# Adafruit_Metro_ESP32-S2.net
KiCad netlist of a schematic drawn in EAGLE
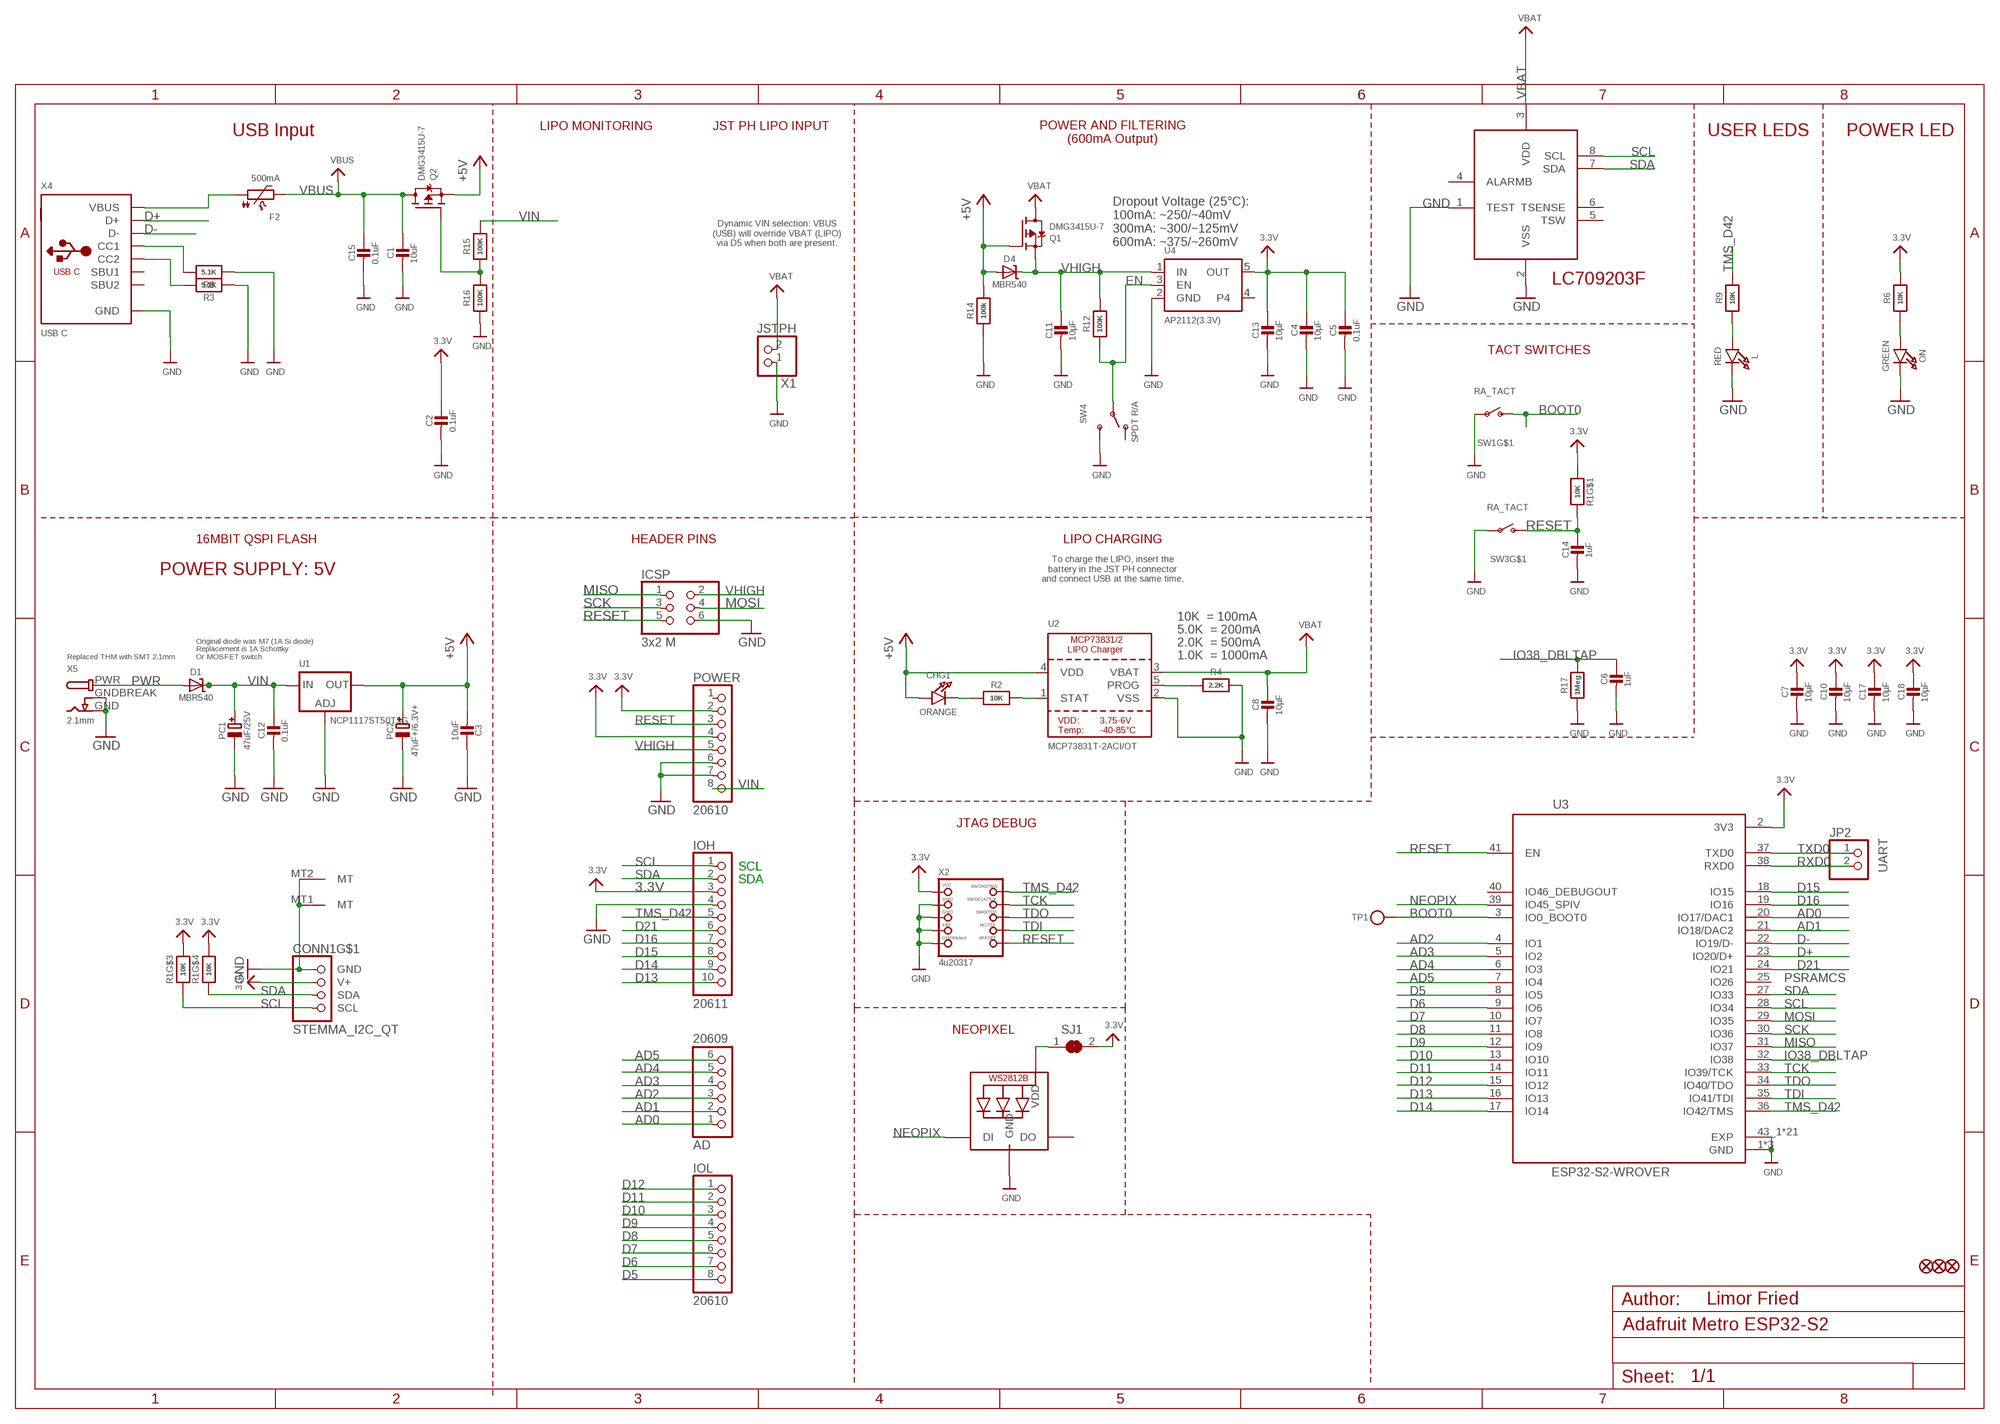
[diagram p0: schematic, sheet 1]

(export (version "E")
  (design (tool "Eeschema 10.0.6"))
  (components
    (comp (ref "AD")
      (value "20609")
      (footprint "eagle-import:1X06_OVALWAVE")
      (libsource (lib "eagle-import") (part "HEADER-1X6OVALWAVE"))
    )
    (comp (ref "C1")
      (value "10uF")
      (footprint "eagle-import:0805-NO")
      (libsource (lib "eagle-import") (part "CAP_CERAMIC0805-NOOUTLINE"))
    )
    (comp (ref "C2")
      (value "0.1uF")
      (footprint "eagle-import:0603-NO")
      (libsource (lib "eagle-import") (part "CAP_CERAMIC0603_NO"))
    )
    (comp (ref "C3")
      (value "10uF")
      (footprint "eagle-import:0805-NO")
      (libsource (lib "eagle-import") (part "CAP_CERAMIC0805-NOOUTLINE"))
    )
    (comp (ref "C4")
      (value "10µF")
      (footprint "eagle-import:0805-NO")
      (libsource (lib "eagle-import") (part "CAP_CERAMIC0805-NOOUTLINE"))
    )
    (comp (ref "C5")
      (value "0.1uF")
      (footprint "eagle-import:0603-NO")
      (libsource (lib "eagle-import") (part "CAP_CERAMIC0603_NO"))
    )
    (comp (ref "C6")
      (value "1uF")
      (footprint "eagle-import:0603-NO")
      (libsource (lib "eagle-import") (part "CAP_CERAMIC0603_NO"))
    )
    (comp (ref "C7")
      (value "10µF")
      (footprint "eagle-import:0805-NO")
      (libsource (lib "eagle-import") (part "CAP_CERAMIC0805-NOOUTLINE"))
    )
    (comp (ref "C8")
      (value "10µF")
      (footprint "eagle-import:0805-NO")
      (libsource (lib "eagle-import") (part "CAP_CERAMIC0805-NOOUTLINE"))
    )
    (comp (ref "C10")
      (value "10µF")
      (footprint "eagle-import:0805-NO")
      (libsource (lib "eagle-import") (part "CAP_CERAMIC0805-NOOUTLINE"))
    )
    (comp (ref "C11")
      (value "10µF")
      (footprint "eagle-import:0805-NO")
      (libsource (lib "eagle-import") (part "CAP_CERAMIC0805-NOOUTLINE"))
    )
    (comp (ref "C12")
      (value "0.1uF")
      (footprint "eagle-import:0603-NO")
      (libsource (lib "eagle-import") (part "CAP_CERAMIC0603_NO"))
    )
    (comp (ref "C13")
      (value "10µF")
      (footprint "eagle-import:0805-NO")
      (libsource (lib "eagle-import") (part "CAP_CERAMIC0805-NOOUTLINE"))
    )
    (comp (ref "C14")
      (value "1uF")
      (footprint "eagle-import:0603-NO")
      (libsource (lib "eagle-import") (part "CAP_CERAMIC0603_NO"))
    )
    (comp (ref "C15")
      (value "0.1uF")
      (footprint "eagle-import:0603-NO")
      (libsource (lib "eagle-import") (part "CAP_CERAMIC0603_NO"))
    )
    (comp (ref "C17")
      (value "10µF")
      (footprint "eagle-import:0805-NO")
      (libsource (lib "eagle-import") (part "CAP_CERAMIC0805-NOOUTLINE"))
    )
    (comp (ref "C18")
      (value "10µF")
      (footprint "eagle-import:0805-NO")
      (libsource (lib "eagle-import") (part "CAP_CERAMIC0805-NOOUTLINE"))
    )
    (comp (ref "CHG1")
      (value "ORANGE")
      (footprint "eagle-import:CHIPLED_0603_NOOUTLINE")
      (libsource (lib "eagle-import") (part "LED0603_NOOUTLINE"))
    )
    (comp (ref "CONN1")
      (value "STEMMA_I2C_QT")
      (footprint "eagle-import:JST_SH4")
      (libsource (lib "eagle-import") (part "STEMMA_I2C_QT"))
    )
    (comp (ref "D1")
      (value "MBR540")
      (footprint "eagle-import:SOD-123")
      (libsource (lib "eagle-import") (part "DIODE-SCHOTTKYSOD-123"))
    )
    (comp (ref "D4")
      (value "MBR540")
      (footprint "eagle-import:SOD-123")
      (libsource (lib "eagle-import") (part "DIODE-SCHOTTKYSOD-123"))
    )
    (comp (ref "F2")
      (value "500mA")
      (footprint "eagle-import:1206")
      (libsource (lib "eagle-import") (part "PTC1206"))
    )
    (comp (ref "FD1")
      (value "FIDUCIAL_1MM")
      (footprint "eagle-import:FIDUCIAL_1MM")
      (libsource (lib "eagle-import") (part "FIDUCIAL_1MM"))
    )
    (comp (ref "FD2")
      (value "FIDUCIAL_1MM")
      (footprint "eagle-import:FIDUCIAL_1MM")
      (libsource (lib "eagle-import") (part "FIDUCIAL_1MM"))
    )
    (comp (ref "FD3")
      (value "FIDUCIAL_1MM")
      (footprint "eagle-import:FIDUCIAL_1MM")
      (libsource (lib "eagle-import") (part "FIDUCIAL_1MM"))
    )
    (comp (ref "IC2")
      (value "LC709203F")
      (footprint "eagle-import:WDFN8_3X4_0.65")
      (libsource (lib "eagle-import") (part "LC709203F"))
    )
    (comp (ref "ICSP")
      (value "3x2 M")
      (footprint "eagle-import:2X03_ROUND_70MIL")
      (libsource (lib "eagle-import") (part "HEADER-2X3"))
    )
    (comp (ref "IOH")
      (value "20611")
      (footprint "eagle-import:1X10_OVALWAVE")
      (libsource (lib "eagle-import") (part "HEADER-1X10OVALWAVE"))
    )
    (comp (ref "IOL")
      (value "20610")
      (footprint "eagle-import:1X08_OVALWAVE")
      (libsource (lib "eagle-import") (part "HEADER-1X8OVALWAVE"))
    )
    (comp (ref "JP2")
      (value "UART")
      (footprint "eagle-import:1X02_ROUND")
      (libsource (lib "eagle-import") (part "HEADER-1X2ROUND"))
    )
    (comp (ref "L")
      (value "RED")
      (footprint "eagle-import:CHIPLED_0603_NOOUTLINE")
      (libsource (lib "eagle-import") (part "LED0603_NOOUTLINE"))
    )
    (comp (ref "LED1")
      (value "WS2812B3535")
      (footprint "eagle-import:LED3535")
      (libsource (lib "eagle-import") (part "WS2812B3535"))
    )
    (comp (ref "ON")
      (value "GREEN")
      (footprint "eagle-import:CHIPLED_0603_NOOUTLINE")
      (libsource (lib "eagle-import") (part "LED0603_NOOUTLINE"))
    )
    (comp (ref "PC1")
      (value "47uF/25V")
      (footprint "eagle-import:PANASONIC_D")
      (libsource (lib "eagle-import") (part "CAP_ELECTROLYTICPANASONIC_D"))
    )
    (comp (ref "PC2")
      (value "47uF+/6.3V+")
      (footprint "eagle-import:PANASONIC_D")
      (libsource (lib "eagle-import") (part "CAP_ELECTROLYTICPANASONIC_D"))
    )
    (comp (ref "POWER")
      (value "20610")
      (footprint "eagle-import:1X08_OVALWAVE")
      (libsource (lib "eagle-import") (part "HEADER-1X8OVALWAVE"))
    )
    (comp (ref "Q1")
      (value "DMG3415U-7")
      (footprint "eagle-import:SOT23-R")
      (libsource (lib "eagle-import") (part "MOSFET-P"))
    )
    (comp (ref "Q2")
      (value "DMG3415U-7")
      (footprint "eagle-import:SOT23-R")
      (libsource (lib "eagle-import") (part "MOSFET-P"))
    )
    (comp (ref "R1")
      (value "10K")
      (footprint "eagle-import:RESPACK_4X0603")
      (libsource (lib "eagle-import") (part "RESISTOR_4PACK"))
    )
    (comp (ref "R2")
      (value "10K")
      (footprint "eagle-import:0603-NO")
      (libsource (lib "eagle-import") (part "RESISTOR_0603_NOOUT"))
    )
    (comp (ref "R3")
      (value "5.1K")
      (footprint "eagle-import:0603-NO")
      (libsource (lib "eagle-import") (part "RESISTOR_0603_NOOUT"))
    )
    (comp (ref "R4")
      (value "2.2K")
      (footprint "eagle-import:0603-NO")
      (libsource (lib "eagle-import") (part "RESISTOR_0603_NOOUT"))
    )
    (comp (ref "R6")
      (value "10K")
      (footprint "eagle-import:0603-NO")
      (libsource (lib "eagle-import") (part "RESISTOR_0603_NOOUT"))
    )
    (comp (ref "R8")
      (value "5.1K")
      (footprint "eagle-import:0603-NO")
      (libsource (lib "eagle-import") (part "RESISTOR_0603_NOOUT"))
    )
    (comp (ref "R9")
      (value "10K")
      (footprint "eagle-import:0603-NO")
      (libsource (lib "eagle-import") (part "RESISTOR_0603_NOOUT"))
    )
    (comp (ref "R12")
      (value "100K")
      (footprint "eagle-import:0603-NO")
      (libsource (lib "eagle-import") (part "RESISTOR_0603_NOOUT"))
    )
    (comp (ref "R14")
      (value "100k")
      (footprint "eagle-import:0603-NO")
      (libsource (lib "eagle-import") (part "RESISTOR_0603_NOOUT"))
    )
    (comp (ref "R15")
      (value "100K")
      (footprint "eagle-import:0603-NO")
      (libsource (lib "eagle-import") (part "RESISTOR_0603_NOOUT"))
    )
    (comp (ref "R16")
      (value "100K")
      (footprint "eagle-import:0603-NO")
      (libsource (lib "eagle-import") (part "RESISTOR_0603_NOOUT"))
    )
    (comp (ref "R17")
      (value "1Meg")
      (footprint "eagle-import:0603-NO")
      (libsource (lib "eagle-import") (part "RESISTOR_0603_NOOUT"))
    )
    (comp (ref "SJ1")
      (value "SOLDERJUMPER_CLOSED")
      (footprint "eagle-import:SOLDERJUMPER_CLOSEDWIRE")
      (libsource (lib "eagle-import") (part "SOLDERJUMPER_CLOSED"))
    )
    (comp (ref "SW1")
      (value "RA_TACT")
      (footprint "eagle-import:SPST_TACTILE_RA")
      (libsource (lib "eagle-import") (part "SWITCH_SPST_TACT_RA"))
    )
    (comp (ref "SW3")
      (value "RA_TACT")
      (footprint "eagle-import:SPST_TACTILE_RA")
      (libsource (lib "eagle-import") (part "SWITCH_SPST_TACT_RA"))
    )
    (comp (ref "SW4")
      (value "SPDT R/A")
      (footprint "eagle-import:SPDT_SMT_SSSS811101")
      (libsource (lib "eagle-import") (part "SWITCH_SPDT"))
    )
    (comp (ref "TP1")
      (value "TESTPOINTROUND1.5MMNO")
      (footprint "eagle-import:TESTPOINT_ROUND_1.5MM_NO")
      (libsource (lib "eagle-import") (part "TESTPOINTROUND1.5MMNO"))
    )
    (comp (ref "U1")
      (value "NCP1117ST50T3G")
      (footprint "eagle-import:SOT223-R")
      (libsource (lib "eagle-import") (part "LM1117SOT223-REFLOW"))
    )
    (comp (ref "U2")
      (value "MCP73831T-2ACI/OT")
      (footprint "eagle-import:SOT23-5")
      (libsource (lib "eagle-import") (part "MCP73831/2"))
    )
    (comp (ref "U3")
      (value "ESP32-S2-WROVER")
      (footprint "eagle-import:MODULE_ESP32-S2-WROVER")
      (fields (field (name "MF") "Espressif Systems"))
      (libsource (lib "eagle-import") (part "ESP32-S2-WROVER"))
    )
    (comp (ref "U4")
      (value "AP2112(3.3V)")
      (footprint "eagle-import:SOT23-5")
      (libsource (lib "eagle-import") (part "VREG_SOT23-5"))
    )
    (comp (ref "X1")
      (value "JSTPH")
      (footprint "eagle-import:JSTPH2_BATT")
      (libsource (lib "eagle-import") (part "CON_JST_PH_2PIN_BATT"))
    )
    (comp (ref "X2")
      (value "4u20317")
      (footprint "eagle-import:2X05_1.27MM_BOX_POSTS")
      (libsource (lib "eagle-import") (part "JTAG-CORTEXBOXPOSTS"))
    )
    (comp (ref "X4")
      (value "USB C")
      (footprint "eagle-import:USB_C_CUSB31-CFM2AX-01-X")
      (libsource (lib "eagle-import") (part "USB_C"))
    )
    (comp (ref "X5")
      (value "2.1mm")
      (footprint "eagle-import:DCJACK_2MM_PTH")
      (libsource (lib "eagle-import") (part "DCBARRELPTH"))
    )
  )
  (nets
    (net (code "1") (name "+5V") (class "Default")
      (node (ref "C3") (pin "2") (pinfunction "2_2") (pintype "passive"))
      (node (ref "CHG1") (pin "A") (pinfunction "A_A") (pintype "passive"))
      (node (ref "D4") (pin "A") (pinfunction "A_A") (pintype "passive"))
      (node (ref "PC2") (pin "+") (pinfunction "+_+") (pintype "passive"))
      (node (ref "Q1") (pin "1") (pinfunction "G_1") (pintype "passive"))
      (node (ref "Q2") (pin "2") (pinfunction "S_2") (pintype "passive"))
      (node (ref "R14") (pin "2") (pinfunction "2_2") (pintype "passive"))
      (node (ref "U1") (pin "2") (pinfunction "OUT_2") (pintype "passive"))
      (node (ref "U1") (pin "4") (pinfunction "OUT_4") (pintype "passive"))
      (node (ref "U2") (pin "4") (pinfunction "VDD_4") (pintype "power_in"))
    )
    (net (code "2") (name "/AD0") (class "Default")
      (node (ref "AD") (pin "1") (pinfunction "1_1") (pintype "passive"))
      (node (ref "U3") (pin "20") (pinfunction "IO17/DAC1_20") (pintype "bidirectional"))
    )
    (net (code "3") (name "/AD1") (class "Default")
      (node (ref "AD") (pin "2") (pinfunction "2_2") (pintype "passive"))
      (node (ref "U3") (pin "21") (pinfunction "IO18/DAC2_21") (pintype "bidirectional"))
    )
    (net (code "4") (name "/AD2") (class "Default")
      (node (ref "AD") (pin "3") (pinfunction "3_3") (pintype "passive"))
      (node (ref "U3") (pin "4") (pinfunction "IO1_4") (pintype "bidirectional"))
    )
    (net (code "5") (name "/AD3") (class "Default")
      (node (ref "AD") (pin "4") (pinfunction "4_4") (pintype "passive"))
      (node (ref "U3") (pin "5") (pinfunction "IO2_5") (pintype "bidirectional"))
    )
    (net (code "6") (name "/AD4") (class "Default")
      (node (ref "AD") (pin "5") (pinfunction "5_5") (pintype "passive"))
      (node (ref "U3") (pin "6") (pinfunction "IO3_6") (pintype "bidirectional"))
    )
    (net (code "7") (name "/AD5") (class "Default")
      (node (ref "AD") (pin "6") (pinfunction "6_6") (pintype "passive"))
      (node (ref "U3") (pin "7") (pinfunction "IO4_7") (pintype "bidirectional"))
    )
    (net (code "8") (name "/BOOT0") (class "Default")
      (node (ref "SW1") (pin "2") (pinfunction "S_2") (pintype "passive"))
      (node (ref "TP1") (pin "P$1") (pinfunction "P$1_P$1") (pintype "bidirectional"))
      (node (ref "U3") (pin "3") (pinfunction "IO0_BOOT0_3") (pintype "bidirectional"))
    )
    (net (code "9") (name "/D+") (class "Default")
      (node (ref "U3") (pin "23") (pinfunction "IO20/D+_23") (pintype "bidirectional"))
      (node (ref "X4") (pin "A6") (pinfunction "D+_A6") (pintype "bidirectional"))
      (node (ref "X4") (pin "B6") (pinfunction "D+_B6") (pintype "bidirectional"))
    )
    (net (code "10") (name "/D-") (class "Default")
      (node (ref "U3") (pin "22") (pinfunction "IO19/D-_22") (pintype "bidirectional"))
      (node (ref "X4") (pin "A7") (pinfunction "D-_A7") (pintype "bidirectional"))
      (node (ref "X4") (pin "B7") (pinfunction "D-_B7") (pintype "bidirectional"))
    )
    (net (code "11") (name "/D5") (class "Default")
      (node (ref "IOL") (pin "8") (pinfunction "8_8") (pintype "passive"))
      (node (ref "U3") (pin "8") (pinfunction "IO5_8") (pintype "bidirectional"))
    )
    (net (code "12") (name "/D6") (class "Default")
      (node (ref "IOL") (pin "7") (pinfunction "7_7") (pintype "passive"))
      (node (ref "U3") (pin "9") (pinfunction "IO6_9") (pintype "bidirectional"))
    )
    (net (code "13") (name "/D7") (class "Default")
      (node (ref "IOL") (pin "6") (pinfunction "6_6") (pintype "passive"))
      (node (ref "U3") (pin "10") (pinfunction "IO7_10") (pintype "bidirectional"))
    )
    (net (code "14") (name "/D8") (class "Default")
      (node (ref "IOL") (pin "5") (pinfunction "5_5") (pintype "passive"))
      (node (ref "U3") (pin "11") (pinfunction "IO8_11") (pintype "bidirectional"))
    )
    (net (code "15") (name "/D9") (class "Default")
      (node (ref "IOL") (pin "4") (pinfunction "4_4") (pintype "passive"))
      (node (ref "U3") (pin "12") (pinfunction "IO9_12") (pintype "bidirectional"))
    )
    (net (code "16") (name "/D10") (class "Default")
      (node (ref "IOL") (pin "3") (pinfunction "3_3") (pintype "passive"))
      (node (ref "U3") (pin "13") (pinfunction "IO10_13") (pintype "bidirectional"))
    )
    (net (code "17") (name "/D11") (class "Default")
      (node (ref "IOL") (pin "2") (pinfunction "2_2") (pintype "passive"))
      (node (ref "U3") (pin "14") (pinfunction "IO11_14") (pintype "bidirectional"))
    )
    (net (code "18") (name "/D12") (class "Default")
      (node (ref "IOL") (pin "1") (pinfunction "1_1") (pintype "passive"))
      (node (ref "U3") (pin "15") (pinfunction "IO12_15") (pintype "bidirectional"))
    )
    (net (code "19") (name "/D13") (class "Default")
      (node (ref "IOH") (pin "10") (pinfunction "10_10") (pintype "passive"))
      (node (ref "U3") (pin "16") (pinfunction "IO13_16") (pintype "bidirectional"))
    )
    (net (code "20") (name "/D14") (class "Default")
      (node (ref "IOH") (pin "9") (pinfunction "9_9") (pintype "passive"))
      (node (ref "U3") (pin "17") (pinfunction "IO14_17") (pintype "bidirectional"))
    )
    (net (code "21") (name "/D15") (class "Default")
      (node (ref "IOH") (pin "8") (pinfunction "8_8") (pintype "passive"))
      (node (ref "U3") (pin "18") (pinfunction "IO15_18") (pintype "bidirectional"))
    )
    (net (code "22") (name "/D16") (class "Default")
      (node (ref "IOH") (pin "7") (pinfunction "7_7") (pintype "passive"))
      (node (ref "U3") (pin "19") (pinfunction "IO16_19") (pintype "bidirectional"))
    )
    (net (code "23") (name "/D21") (class "Default")
      (node (ref "IOH") (pin "6") (pinfunction "6_6") (pintype "passive"))
      (node (ref "U3") (pin "24") (pinfunction "IO21_24") (pintype "bidirectional"))
    )
    (net (code "24") (name "/EN") (class "Default")
      (node (ref "R12") (pin "1") (pinfunction "1_1") (pintype "passive"))
      (node (ref "SW4") (pin "B") (pinfunction "P_B") (pintype "passive"))
      (node (ref "U4") (pin "3") (pinfunction "EN_3") (pintype "input"))
    )
    (net (code "25") (name "/IO38_DBLTAP") (class "Default")
      (node (ref "C6") (pin "1") (pinfunction "1_1") (pintype "passive"))
      (node (ref "R17") (pin "2") (pinfunction "2_2") (pintype "passive"))
      (node (ref "U3") (pin "32") (pinfunction "IO38_32") (pintype "bidirectional"))
    )
    (net (code "26") (name "/MISO") (class "Default")
      (node (ref "ICSP") (pin "1") (pinfunction "1_1") (pintype "passive"))
      (node (ref "U3") (pin "31") (pinfunction "IO37_31") (pintype "bidirectional"))
    )
    (net (code "27") (name "/MOSI") (class "Default")
      (node (ref "ICSP") (pin "4") (pinfunction "4_4") (pintype "passive"))
      (node (ref "U3") (pin "29") (pinfunction "IO35_29") (pintype "input"))
    )
    (net (code "28") (name "/NEOPIX") (class "Default")
      (node (ref "LED1") (pin "1") (pinfunction "DI_1") (pintype "input"))
      (node (ref "U3") (pin "39") (pinfunction "IO45_SPIV_39") (pintype "bidirectional"))
    )
    (net (code "29") (name "/PWR") (class "Default")
      (node (ref "D1") (pin "A") (pinfunction "A_A") (pintype "passive"))
      (node (ref "X5") (pin "PWR") (pinfunction "PWR_PWR") (pintype "power_in"))
    )
    (net (code "30") (name "/RESET") (class "Default")
      (node (ref "C14") (pin "1") (pinfunction "1_1") (pintype "passive"))
      (node (ref "ICSP") (pin "5") (pinfunction "5_5") (pintype "passive"))
      (node (ref "POWER") (pin "3") (pinfunction "3_3") (pintype "passive"))
      (node (ref "R1") (pin "8") (pinfunction "2_8") (pintype "passive"))
      (node (ref "SW3") (pin "2") (pinfunction "S_2") (pintype "passive"))
      (node (ref "U3") (pin "41") (pinfunction "EN_41") (pintype "input"))
      (node (ref "X2") (pin "10") (pinfunction "NRESET_10") (pintype "bidirectional"))
    )
    (net (code "31") (name "/RXD0") (class "Default")
      (node (ref "JP2") (pin "2") (pinfunction "2_2") (pintype "passive"))
      (node (ref "U3") (pin "38") (pinfunction "RXD0_38") (pintype "bidirectional"))
    )
    (net (code "32") (name "/SCK") (class "Default")
      (node (ref "ICSP") (pin "3") (pinfunction "3_3") (pintype "passive"))
      (node (ref "U3") (pin "30") (pinfunction "IO36_30") (pintype "bidirectional"))
    )
    (net (code "33") (name "/SCL") (class "Default")
      (node (ref "CONN1") (pin "4") (pinfunction "SCL_4") (pintype "passive"))
      (node (ref "IC2") (pin "8") (pinfunction "SCL_8") (pintype "bidirectional"))
      (node (ref "IOH") (pin "1") (pinfunction "1_1") (pintype "passive"))
      (node (ref "R1") (pin "3") (pinfunction "1_3") (pintype "passive"))
      (node (ref "U3") (pin "28") (pinfunction "IO34_28") (pintype "input"))
    )
    (net (code "34") (name "/SDA") (class "Default")
      (node (ref "CONN1") (pin "3") (pinfunction "SDA_3") (pintype "passive"))
      (node (ref "IC2") (pin "7") (pinfunction "SDA_7") (pintype "bidirectional"))
      (node (ref "IOH") (pin "2") (pinfunction "2_2") (pintype "passive"))
      (node (ref "R1") (pin "4") (pinfunction "1_4") (pintype "passive"))
      (node (ref "U3") (pin "27") (pinfunction "IO33_27") (pintype "bidirectional"))
    )
    (net (code "35") (name "/TCK") (class "Default")
      (node (ref "U3") (pin "33") (pinfunction "IO39/TCK_33") (pintype "bidirectional"))
      (node (ref "X2") (pin "4") (pinfunction "SWDCLK_4") (pintype "bidirectional"))
    )
    (net (code "36") (name "/TDI") (class "Default")
      (node (ref "U3") (pin "35") (pinfunction "IO41/TDI_35") (pintype "bidirectional"))
      (node (ref "X2") (pin "8") (pinfunction "TDI_8") (pintype "bidirectional"))
    )
    (net (code "37") (name "/TDO") (class "Default")
      (node (ref "U3") (pin "34") (pinfunction "IO40/TDO_34") (pintype "bidirectional"))
      (node (ref "X2") (pin "6") (pinfunction "SWO_6") (pintype "bidirectional"))
    )
    (net (code "38") (name "/TMS_D42") (class "Default")
      (node (ref "IOH") (pin "5") (pinfunction "5_5") (pintype "passive"))
      (node (ref "R9") (pin "2") (pinfunction "2_2") (pintype "passive"))
      (node (ref "U3") (pin "36") (pinfunction "IO42/TMS_36") (pintype "bidirectional"))
      (node (ref "X2") (pin "2") (pinfunction "SWDIO_2") (pintype "bidirectional"))
    )
    (net (code "39") (name "/TSENSE") (class "Default")
      (node (ref "IC2") (pin "6") (pinfunction "TSENSE_6") (pintype "power_in"))
    )
    (net (code "40") (name "/TXD0") (class "Default")
      (node (ref "JP2") (pin "1") (pinfunction "1_1") (pintype "passive"))
      (node (ref "U3") (pin "37") (pinfunction "TXD0_37") (pintype "bidirectional"))
    )
    (net (code "41") (name "/VHIGH") (class "Default")
      (node (ref "C11") (pin "1") (pinfunction "1_1") (pintype "passive"))
      (node (ref "D4") (pin "C") (pinfunction "C_C") (pintype "passive"))
      (node (ref "ICSP") (pin "2") (pinfunction "2_2") (pintype "passive"))
      (node (ref "POWER") (pin "5") (pinfunction "5_5") (pintype "passive"))
      (node (ref "Q1") (pin "2") (pinfunction "S_2") (pintype "passive"))
      (node (ref "R12") (pin "2") (pinfunction "2_2") (pintype "passive"))
      (node (ref "U4") (pin "1") (pinfunction "IN_1") (pintype "power_in"))
    )
    (net (code "42") (name "/VIN") (class "Default")
      (node (ref "C12") (pin "1") (pinfunction "1_1") (pintype "passive"))
      (node (ref "D1") (pin "C") (pinfunction "C_C") (pintype "passive"))
      (node (ref "PC1") (pin "+") (pinfunction "+_+") (pintype "passive"))
      (node (ref "POWER") (pin "8") (pinfunction "8_8") (pintype "passive"))
      (node (ref "R15") (pin "2") (pinfunction "2_2") (pintype "passive"))
      (node (ref "U1") (pin "3") (pinfunction "IN_3") (pintype "input"))
    )
    (net (code "43") (name "3.3V") (class "Default")
      (node (ref "C10") (pin "1") (pinfunction "1_1") (pintype "passive"))
      (node (ref "C13") (pin "1") (pinfunction "1_1") (pintype "passive"))
      (node (ref "C17") (pin "1") (pinfunction "1_1") (pintype "passive"))
      (node (ref "C18") (pin "1") (pinfunction "1_1") (pintype "passive"))
      (node (ref "C2") (pin "1") (pinfunction "1_1") (pintype "passive"))
      (node (ref "C4") (pin "1") (pinfunction "1_1") (pintype "passive"))
      (node (ref "C5") (pin "1") (pinfunction "1_1") (pintype "passive"))
      (node (ref "C7") (pin "1") (pinfunction "1_1") (pintype "passive"))
      (node (ref "CONN1") (pin "2") (pinfunction "V+_2") (pintype "passive"))
      (node (ref "IOH") (pin "3") (pinfunction "3_3") (pintype "passive"))
      (node (ref "POWER") (pin "2") (pinfunction "2_2") (pintype "passive"))
      (node (ref "POWER") (pin "4") (pinfunction "4_4") (pintype "passive"))
      (node (ref "R1") (pin "1") (pinfunction "1_1") (pintype "passive"))
      (node (ref "R1") (pin "5") (pinfunction "2_5") (pintype "passive"))
      (node (ref "R1") (pin "6") (pinfunction "2_6") (pintype "passive"))
      (node (ref "R6") (pin "2") (pinfunction "2_2") (pintype "passive"))
      (node (ref "SJ1") (pin "2") (pinfunction "2_2") (pintype "passive"))
      (node (ref "U3") (pin "2") (pinfunction "3V3_2") (pintype "power_in"))
      (node (ref "U4") (pin "5") (pinfunction "OUT_5") (pintype "power_in"))
      (node (ref "X2") (pin "1") (pinfunction "VCC_1") (pintype "power_in"))
    )
    (net (code "44") (name "GND") (class "Default")
      (node (ref "C1") (pin "2") (pinfunction "2_2") (pintype "passive"))
      (node (ref "C10") (pin "2") (pinfunction "2_2") (pintype "passive"))
      (node (ref "C11") (pin "2") (pinfunction "2_2") (pintype "passive"))
      (node (ref "C12") (pin "2") (pinfunction "2_2") (pintype "passive"))
      (node (ref "C13") (pin "2") (pinfunction "2_2") (pintype "passive"))
      (node (ref "C14") (pin "2") (pinfunction "2_2") (pintype "passive"))
      (node (ref "C15") (pin "2") (pinfunction "2_2") (pintype "passive"))
      (node (ref "C17") (pin "2") (pinfunction "2_2") (pintype "passive"))
      (node (ref "C18") (pin "2") (pinfunction "2_2") (pintype "passive"))
      (node (ref "C2") (pin "2") (pinfunction "2_2") (pintype "passive"))
      (node (ref "C3") (pin "1") (pinfunction "1_1") (pintype "passive"))
      (node (ref "C4") (pin "2") (pinfunction "2_2") (pintype "passive"))
      (node (ref "C5") (pin "2") (pinfunction "2_2") (pintype "passive"))
      (node (ref "C6") (pin "2") (pinfunction "2_2") (pintype "passive"))
      (node (ref "C7") (pin "2") (pinfunction "2_2") (pintype "passive"))
      (node (ref "C8") (pin "2") (pinfunction "2_2") (pintype "passive"))
      (node (ref "CONN1") (pin "1") (pinfunction "GND_1") (pintype "passive"))
      (node (ref "CONN1") (pin "MT1") (pinfunction "MT_MT1") (pintype "bidirectional"))
      (node (ref "CONN1") (pin "MT2") (pinfunction "MT_MT2") (pintype "bidirectional"))
      (node (ref "IC2") (pin "1") (pinfunction "TEST_1") (pintype "bidirectional"))
      (node (ref "IC2") (pin "2") (pinfunction "VSS_2") (pintype "power_in"))
      (node (ref "ICSP") (pin "6") (pinfunction "6_6") (pintype "passive"))
      (node (ref "IOH") (pin "4") (pinfunction "4_4") (pintype "passive"))
      (node (ref "L") (pin "C") (pinfunction "C_C") (pintype "passive"))
      (node (ref "LED1") (pin "4") (pinfunction "GND_4") (pintype "power_in"))
      (node (ref "ON") (pin "C") (pinfunction "C_C") (pintype "passive"))
      (node (ref "PC1") (pin "-") (pinfunction "-_-") (pintype "passive"))
      (node (ref "PC2") (pin "-") (pinfunction "-_-") (pintype "passive"))
      (node (ref "POWER") (pin "6") (pinfunction "6_6") (pintype "passive"))
      (node (ref "POWER") (pin "7") (pinfunction "7_7") (pintype "passive"))
      (node (ref "R14") (pin "1") (pinfunction "1_1") (pintype "passive"))
      (node (ref "R16") (pin "1") (pinfunction "1_1") (pintype "passive"))
      (node (ref "R17") (pin "1") (pinfunction "1_1") (pintype "passive"))
      (node (ref "R3") (pin "1") (pinfunction "1_1") (pintype "passive"))
      (node (ref "R4") (pin "2") (pinfunction "2_2") (pintype "passive"))
      (node (ref "R8") (pin "1") (pinfunction "1_1") (pintype "passive"))
      (node (ref "SW1") (pin "1") (pinfunction "P_1") (pintype "passive"))
      (node (ref "SW3") (pin "1") (pinfunction "P_1") (pintype "passive"))
      (node (ref "SW4") (pin "C") (pinfunction "S_C") (pintype "passive"))
      (node (ref "U1") (pin "1") (pinfunction "ADJ_1") (pintype "input"))
      (node (ref "U2") (pin "2") (pinfunction "VSS_2") (pintype "power_in"))
      (node (ref "U3") (pin "1") (pinfunction "GND_1") (pintype "power_in"))
      (node (ref "U3") (pin "26") (pinfunction "GND_26") (pintype "power_in"))
      (node (ref "U3") (pin "42") (pinfunction "GND_42") (pintype "power_in"))
      (node (ref "U3") (pin "43_1") (pinfunction "EXP_43_1") (pintype "power_in"))
      (node (ref "U3") (pin "43_10") (pinfunction "EXP_43_10") (pintype "power_in"))
      (node (ref "U3") (pin "43_11") (pinfunction "EXP_43_11") (pintype "power_in"))
      (node (ref "U3") (pin "43_12") (pinfunction "EXP_43_12") (pintype "power_in"))
      (node (ref "U3") (pin "43_13") (pinfunction "EXP_43_13") (pintype "power_in"))
      (node (ref "U3") (pin "43_14") (pinfunction "EXP_43_14") (pintype "power_in"))
      (node (ref "U3") (pin "43_15") (pinfunction "EXP_43_15") (pintype "power_in"))
      (node (ref "U3") (pin "43_16") (pinfunction "EXP_43_16") (pintype "power_in"))
      (node (ref "U3") (pin "43_17") (pinfunction "EXP_43_17") (pintype "power_in"))
      (node (ref "U3") (pin "43_18") (pinfunction "EXP_43_18") (pintype "power_in"))
      (node (ref "U3") (pin "43_19") (pinfunction "EXP_43_19") (pintype "power_in"))
      (node (ref "U3") (pin "43_2") (pinfunction "EXP_43_2") (pintype "power_in"))
      (node (ref "U3") (pin "43_20") (pinfunction "EXP_43_20") (pintype "power_in"))
      (node (ref "U3") (pin "43_21") (pinfunction "EXP_43_21") (pintype "power_in"))
      (node (ref "U3") (pin "43_3") (pinfunction "EXP_43_3") (pintype "power_in"))
      (node (ref "U3") (pin "43_4") (pinfunction "EXP_43_4") (pintype "power_in"))
      (node (ref "U3") (pin "43_5") (pinfunction "EXP_43_5") (pintype "power_in"))
      (node (ref "U3") (pin "43_6") (pinfunction "EXP_43_6") (pintype "power_in"))
      (node (ref "U3") (pin "43_7") (pinfunction "EXP_43_7") (pintype "power_in"))
      (node (ref "U3") (pin "43_8") (pinfunction "EXP_43_8") (pintype "power_in"))
      (node (ref "U3") (pin "43_9") (pinfunction "EXP_43_9") (pintype "power_in"))
      (node (ref "U4") (pin "2") (pinfunction "GND_2") (pintype "power_in"))
      (node (ref "X1") (pin "1") (pinfunction "1_1") (pintype "passive"))
      (node (ref "X2") (pin "3") (pinfunction "GND_3") (pintype "power_in"))
      (node (ref "X2") (pin "5") (pinfunction "GND_5") (pintype "power_in"))
      (node (ref "X2") (pin "7") (pinfunction "KEY_7") (pintype "bidirectional"))
      (node (ref "X2") (pin "9") (pinfunction "GNDDETECT_9") (pintype "bidirectional"))
      (node (ref "X4") (pin "A1B12") (pinfunction "GND_A1B12") (pintype "power_in"))
      (node (ref "X4") (pin "B1A12") (pinfunction "GND_B1A12") (pintype "power_in"))
      (node (ref "X5") (pin "GND") (pinfunction "GND_GND") (pintype "power_in"))
      (node (ref "X5") (pin "GNDBREAK") (pinfunction "GNDBREAK_GNDBREAK") (pintype "power_in"))
    )
    (net (code "45") (name "Net-(CHG1-PadC)") (class "Default")
      (node (ref "CHG1") (pin "C") (pinfunction "C_C") (pintype "passive"))
      (node (ref "R2") (pin "1") (pinfunction "1_1") (pintype "passive"))
    )
    (net (code "46") (name "Net-(F2-Pad1)") (class "Default")
      (node (ref "F2") (pin "1") (pinfunction "1_1") (pintype "passive"))
      (node (ref "X4") (pin "A4B9") (pinfunction "VBUS_A4B9") (pintype "power_in"))
      (node (ref "X4") (pin "B4A9") (pinfunction "VBUS_B4A9") (pintype "power_in"))
    )
    (net (code "47") (name "Net-(L-PadA)") (class "Default")
      (node (ref "L") (pin "A") (pinfunction "A_A") (pintype "passive"))
      (node (ref "R9") (pin "1") (pinfunction "1_1") (pintype "passive"))
    )
    (net (code "48") (name "Net-(LED1-VDD)") (class "Default")
      (node (ref "LED1") (pin "2") (pinfunction "VDD_2") (pintype "power_in"))
      (node (ref "SJ1") (pin "1") (pinfunction "1_1") (pintype "passive"))
    )
    (net (code "49") (name "Net-(ON-PadA)") (class "Default")
      (node (ref "ON") (pin "A") (pinfunction "A_A") (pintype "passive"))
      (node (ref "R6") (pin "1") (pinfunction "1_1") (pintype "passive"))
    )
    (net (code "50") (name "Net-(Q2-G)") (class "Default")
      (node (ref "Q2") (pin "1") (pinfunction "G_1") (pintype "passive"))
      (node (ref "R15") (pin "1") (pinfunction "1_1") (pintype "passive"))
      (node (ref "R16") (pin "2") (pinfunction "2_2") (pintype "passive"))
    )
    (net (code "51") (name "Net-(U2-PROG)") (class "Default")
      (node (ref "R4") (pin "1") (pinfunction "1_1") (pintype "passive"))
      (node (ref "U2") (pin "5") (pinfunction "PROG_5") (pintype "input"))
    )
    (net (code "52") (name "Net-(U2-STAT)") (class "Default")
      (node (ref "R2") (pin "2") (pinfunction "2_2") (pintype "passive"))
      (node (ref "U2") (pin "1") (pinfunction "STAT_1") (pintype "output"))
    )
    (net (code "53") (name "Net-(X4-CC1)") (class "Default")
      (node (ref "R8") (pin "2") (pinfunction "2_2") (pintype "passive"))
      (node (ref "X4") (pin "A5") (pinfunction "CC1_A5") (pintype "bidirectional"))
    )
    (net (code "54") (name "Net-(X4-CC2)") (class "Default")
      (node (ref "R3") (pin "2") (pinfunction "2_2") (pintype "passive"))
      (node (ref "X4") (pin "B5") (pinfunction "CC2_B5") (pintype "bidirectional"))
    )
    (net (code "55") (name "VBAT") (class "Default")
      (node (ref "C8") (pin "1") (pinfunction "1_1") (pintype "passive"))
      (node (ref "IC2") (pin "3") (pinfunction "VDD_3") (pintype "power_in"))
      (node (ref "Q1") (pin "3") (pinfunction "D_3") (pintype "passive"))
      (node (ref "U2") (pin "3") (pinfunction "VBAT_3") (pintype "power_in"))
      (node (ref "X1") (pin "2") (pinfunction "2_2") (pintype "passive"))
    )
    (net (code "56") (name "VBUS") (class "Default")
      (node (ref "C1") (pin "1") (pinfunction "1_1") (pintype "passive"))
      (node (ref "C15") (pin "1") (pinfunction "1_1") (pintype "passive"))
      (node (ref "F2") (pin "2") (pinfunction "2_2") (pintype "passive"))
      (node (ref "Q2") (pin "3") (pinfunction "D_3") (pintype "passive"))
    )
    (net (code "57") (name "unconnected-(IC2-ALARMB-Pad4)") (class "Default")
      (node (ref "IC2") (pin "4") (pinfunction "ALARMB_4") (pintype "output"))
    )
    (net (code "58") (name "unconnected-(IC2-TSW-Pad5)") (class "Default")
      (node (ref "IC2") (pin "5") (pinfunction "TSW_5") (pintype "input"))
    )
    (net (code "59") (name "unconnected-(LED1-DO-Pad3)") (class "Default")
      (node (ref "LED1") (pin "3") (pinfunction "DO_3") (pintype "output"))
    )
    (net (code "60") (name "unconnected-(POWER-Pad1)") (class "Default")
      (node (ref "POWER") (pin "1") (pinfunction "1_1") (pintype "passive"))
    )
    (net (code "61") (name "unconnected-(SW4-O-PadA)") (class "Default")
      (node (ref "SW4") (pin "A") (pinfunction "O_A") (pintype "passive"))
    )
    (net (code "62") (name "unconnected-(U3-IO26-Pad25)") (class "Default")
      (node (ref "U3") (pin "25") (pinfunction "IO26_25") (pintype "bidirectional"))
    )
    (net (code "63") (name "unconnected-(U3-IO46_DEBUGOUT-Pad40)") (class "Default")
      (node (ref "U3") (pin "40") (pinfunction "IO46_DEBUGOUT_40") (pintype "input"))
    )
    (net (code "64") (name "unconnected-(U4-P4-Pad4)") (class "Default")
      (node (ref "U4") (pin "4") (pinfunction "P4_4") (pintype "bidirectional"))
    )
    (net (code "65") (name "unconnected-(X4-SBU1-PadA8)") (class "Default")
      (node (ref "X4") (pin "A8") (pinfunction "SBU1_A8") (pintype "bidirectional"))
    )
    (net (code "66") (name "unconnected-(X4-SBU2-PadB8)") (class "Default")
      (node (ref "X4") (pin "B8") (pinfunction "SBU2_B8") (pintype "bidirectional"))
    )
  )
)
